# USB_Audio.net
KiCad netlist of a schematic drawn in Altium Designer
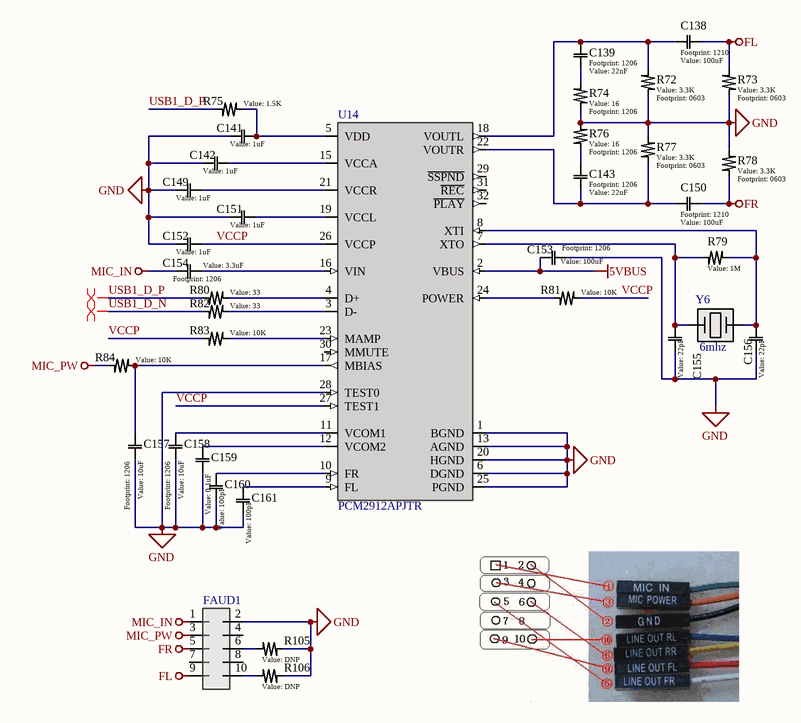
[diagram p0: USB_Audio.SchDoc]

(export (version "E")
  (design (tool "Eeschema 10.0.6"))
  (components
    (comp (ref "C138")
      (value "100uF")
      (footprint "1210")
      (fields
        (field (name "VOLTAGE") ">10V")
        (field (name "TOLERANCE") "10%")
        (field (name "Comment") "Generic Capacitor")
      )
      (libsource (lib "Capacitors") (part "Generic Capacitor"))
    )
    (comp (ref "C139")
      (value "22nF")
      (footprint "1206")
      (fields
        (field (name "VOLTAGE") ">10V")
        (field (name "TOLERANCE") "10%")
        (field (name "Comment") "Generic Capacitor")
      )
      (libsource (lib "Capacitors") (part "Generic Capacitor"))
    )
    (comp (ref "C141")
      (value "1uF")
      (footprint "0603")
      (fields
        (field (name "VOLTAGE") ">10V")
        (field (name "TOLERANCE") "10%")
        (field (name "Comment") "Generic Capacitor")
      )
      (libsource (lib "Capacitors") (part "Generic Capacitor"))
    )
    (comp (ref "C142")
      (value "1uF")
      (footprint "0603")
      (fields
        (field (name "VOLTAGE") ">10V")
        (field (name "TOLERANCE") "10%")
        (field (name "Comment") "Generic Capacitor")
      )
      (libsource (lib "Capacitors") (part "Generic Capacitor"))
    )
    (comp (ref "C143")
      (value "22nF")
      (footprint "1206")
      (fields
        (field (name "VOLTAGE") ">10V")
        (field (name "TOLERANCE") "10%")
        (field (name "Comment") "Generic Capacitor")
      )
      (libsource (lib "Capacitors") (part "Generic Capacitor"))
    )
    (comp (ref "C149")
      (value "1uF")
      (footprint "0603")
      (fields
        (field (name "VOLTAGE") ">10V")
        (field (name "TOLERANCE") "10%")
        (field (name "Comment") "Generic Capacitor")
      )
      (libsource (lib "Capacitors") (part "Generic Capacitor"))
    )
    (comp (ref "C150")
      (value "100uF")
      (footprint "1210")
      (fields
        (field (name "VOLTAGE") ">10V")
        (field (name "TOLERANCE") "10%")
        (field (name "Comment") "Generic Capacitor")
      )
      (libsource (lib "Capacitors") (part "Generic Capacitor"))
    )
    (comp (ref "C151")
      (value "1uF")
      (footprint "0603")
      (fields
        (field (name "VOLTAGE") ">10V")
        (field (name "TOLERANCE") "10%")
        (field (name "Comment") "Generic Capacitor")
      )
      (libsource (lib "Capacitors") (part "Generic Capacitor"))
    )
    (comp (ref "C152")
      (value "1uF")
      (footprint "0603")
      (fields
        (field (name "VOLTAGE") ">10V")
        (field (name "TOLERANCE") "10%")
        (field (name "Comment") "Generic Capacitor")
      )
      (libsource (lib "Capacitors") (part "Generic Capacitor"))
    )
    (comp (ref "C153")
      (value "100uF")
      (footprint "1206")
      (fields
        (field (name "VOLTAGE") ">10V")
        (field (name "TOLERANCE") "10%")
        (field (name "Comment") "Generic Capacitor")
      )
      (libsource (lib "Capacitors") (part "Generic Capacitor"))
    )
    (comp (ref "C154")
      (value "3.3uF")
      (footprint "1206")
      (fields
        (field (name "VOLTAGE") ">10V")
        (field (name "TOLERANCE") "10%")
        (field (name "Comment") "Generic Capacitor")
      )
      (libsource (lib "Capacitors") (part "Generic Capacitor"))
    )
    (comp (ref "C155")
      (value "22pF")
      (footprint "0603")
      (fields
        (field (name "VOLTAGE") ">10V")
        (field (name "TOLERANCE") "10%")
        (field (name "Comment") "Generic Capacitor")
      )
      (libsource (lib "Capacitors") (part "Generic Capacitor"))
    )
    (comp (ref "C156")
      (value "22pF")
      (footprint "0603")
      (fields
        (field (name "VOLTAGE") ">10V")
        (field (name "TOLERANCE") "10%")
        (field (name "Comment") "Generic Capacitor")
      )
      (libsource (lib "Capacitors") (part "Generic Capacitor"))
    )
    (comp (ref "C157")
      (value "10uF")
      (footprint "1206")
      (fields
        (field (name "VOLTAGE") ">10V")
        (field (name "TOLERANCE") "10%")
        (field (name "Comment") "Generic Capacitor")
      )
      (libsource (lib "Capacitors") (part "Generic Capacitor"))
    )
    (comp (ref "C158")
      (value "10uF")
      (footprint "1206")
      (fields
        (field (name "VOLTAGE") ">10V")
        (field (name "TOLERANCE") "10%")
        (field (name "Comment") "Generic Capacitor")
      )
      (libsource (lib "Capacitors") (part "Generic Capacitor"))
    )
    (comp (ref "C159")
      (value "0.1uF")
      (footprint "0603")
      (fields
        (field (name "VOLTAGE") ">10V")
        (field (name "TOLERANCE") "10%")
        (field (name "Comment") "Generic Capacitor")
      )
      (libsource (lib "Capacitors") (part "Generic Capacitor"))
    )
    (comp (ref "C160")
      (value "100pF")
      (footprint "0603")
      (fields
        (field (name "VOLTAGE") ">10V")
        (field (name "TOLERANCE") "10%")
        (field (name "Comment") "Generic Capacitor")
      )
      (libsource (lib "Capacitors") (part "Generic Capacitor"))
    )
    (comp (ref "C161")
      (value "100pF")
      (footprint "0603")
      (fields
        (field (name "VOLTAGE") ">10V")
        (field (name "TOLERANCE") "10%")
        (field (name "Comment") "Generic Capacitor")
      )
      (libsource (lib "Capacitors") (part "Generic Capacitor"))
    )
    (comp (ref "FAUD1")
      (value "10pinMobo")
      (footprint "10pinMobo")
      (description "10pin motherboard jack")
      (libsource (lib "Connectors") (part "10pinMobo"))
    )
    (comp (ref "R72")
      (value "3.3K")
      (footprint "0603")
      (fields
        (field (name "TOLERANCE") "1%")
        (field (name "POWER") "1/10W")
        (field (name "Comment") "Generic Resistor")
      )
      (libsource (lib "Resistors") (part "Generic Resistor"))
    )
    (comp (ref "R73")
      (value "3.3K")
      (footprint "0603")
      (fields
        (field (name "TOLERANCE") "1%")
        (field (name "POWER") "1/10W")
        (field (name "Comment") "Generic Resistor")
      )
      (libsource (lib "Resistors") (part "Generic Resistor"))
    )
    (comp (ref "R74")
      (value "16")
      (footprint "1206")
      (fields
        (field (name "TOLERANCE") "1%")
        (field (name "POWER") "1/10W")
        (field (name "Comment") "Generic Resistor")
      )
      (libsource (lib "Resistors") (part "Generic Resistor"))
    )
    (comp (ref "R75")
      (value "1.5K")
      (footprint "0603")
      (fields
        (field (name "TOLERANCE") "1%")
        (field (name "POWER") "1/10W")
        (field (name "Comment") "Generic Resistor")
      )
      (libsource (lib "Resistors") (part "Generic Resistor"))
    )
    (comp (ref "R76")
      (value "16")
      (footprint "1206")
      (fields
        (field (name "TOLERANCE") "1%")
        (field (name "POWER") "1/10W")
        (field (name "Comment") "Generic Resistor")
      )
      (libsource (lib "Resistors") (part "Generic Resistor"))
    )
    (comp (ref "R77")
      (value "3.3K")
      (footprint "0603")
      (fields
        (field (name "TOLERANCE") "1%")
        (field (name "POWER") "1/10W")
        (field (name "Comment") "Generic Resistor")
      )
      (libsource (lib "Resistors") (part "Generic Resistor"))
    )
    (comp (ref "R78")
      (value "3.3K")
      (footprint "0603")
      (fields
        (field (name "TOLERANCE") "1%")
        (field (name "POWER") "1/10W")
        (field (name "Comment") "Generic Resistor")
      )
      (libsource (lib "Resistors") (part "Generic Resistor"))
    )
    (comp (ref "R79")
      (value "1M")
      (footprint "0603")
      (fields
        (field (name "TOLERANCE") "1%")
        (field (name "POWER") "1/10W")
        (field (name "Comment") "Generic Resistor")
      )
      (libsource (lib "Resistors") (part "Generic Resistor"))
    )
    (comp (ref "R80")
      (value "33")
      (footprint "0603")
      (fields
        (field (name "TOLERANCE") "1%")
        (field (name "POWER") "1/10W")
        (field (name "Comment") "Generic Resistor")
      )
      (libsource (lib "Resistors") (part "Generic Resistor"))
    )
    (comp (ref "R81")
      (value "10K")
      (footprint "0603")
      (fields
        (field (name "TOLERANCE") "1%")
        (field (name "POWER") "1/10W")
        (field (name "Comment") "Generic Resistor")
      )
      (libsource (lib "Resistors") (part "Generic Resistor"))
    )
    (comp (ref "R82")
      (value "33")
      (footprint "0603")
      (fields
        (field (name "TOLERANCE") "1%")
        (field (name "POWER") "1/10W")
        (field (name "Comment") "Generic Resistor")
      )
      (libsource (lib "Resistors") (part "Generic Resistor"))
    )
    (comp (ref "R83")
      (value "10K")
      (footprint "0603")
      (fields
        (field (name "TOLERANCE") "1%")
        (field (name "POWER") "1/10W")
        (field (name "Comment") "Generic Resistor")
      )
      (libsource (lib "Resistors") (part "Generic Resistor"))
    )
    (comp (ref "R84")
      (value "10K")
      (footprint "0603")
      (fields
        (field (name "TOLERANCE") "1%")
        (field (name "POWER") "1/10W")
        (field (name "Comment") "Generic Resistor")
      )
      (libsource (lib "Resistors") (part "Generic Resistor"))
    )
    (comp (ref "R105")
      (value "DNP")
      (footprint "0603")
      (fields
        (field (name "TOLERANCE") "1%")
        (field (name "POWER") "1/10W")
        (field (name "Comment") "Generic Resistor")
      )
      (libsource (lib "Resistors") (part "Generic Resistor"))
    )
    (comp (ref "R106")
      (value "DNP")
      (footprint "0603")
      (fields
        (field (name "TOLERANCE") "1%")
        (field (name "POWER") "1/10W")
        (field (name "Comment") "Generic Resistor")
      )
      (libsource (lib "Resistors") (part "Generic Resistor"))
    )
    (comp (ref "U14")
      (value "PCM2912APJTR")
      (footprint "32-TQFP")
      (fields (field (name "MF") "Texas Instruments"))
      (libsource (lib "Misc ICs") (part "PCM2912APJTR"))
    )
    (comp (ref "Y6")
      (value "6mhz")
      (footprint "HC-49S-SMD")
      (description "6MHz Surface Mount Crystal 20pF ±20ppm ±30ppm HC-49S-SMD Crystals")
      (libsource (lib "Clock ICs") (part "H6OEL89CSC-SUGYLC-6M"))
    )
  )
  (nets
    (net (code "1") (name "/USB1_D_N") (class "Default")
      (node (ref "R82") (pin "2") (pinfunction "2_2") (pintype "passive"))
    )
    (net (code "2") (name "/USB1_D_P") (class "Default")
      (node (ref "R75") (pin "2") (pinfunction "2_2") (pintype "passive"))
      (node (ref "R80") (pin "2") (pinfunction "2_2") (pintype "passive"))
    )
    (net (code "3") (name "/VCCP") (class "Default")
      (node (ref "C152") (pin "2") (pinfunction "2_2") (pintype "passive"))
      (node (ref "R81") (pin "1") (pinfunction "1_1") (pintype "passive"))
      (node (ref "R83") (pin "2") (pinfunction "2_2") (pintype "passive"))
      (node (ref "U14") (pin "26") (pinfunction "VCCP_26") (pintype "power_in"))
      (node (ref "U14") (pin "27") (pinfunction "TEST1_27") (pintype "input"))
    )
    (net (code "4") (name "5VBUS") (class "Default")
      (node (ref "C153") (pin "1") (pinfunction "1_1") (pintype "passive"))
      (node (ref "U14") (pin "2") (pinfunction "VBUS_2") (pintype "input"))
    )
    (net (code "5") (name "FL") (class "Default")
      (node (ref "C138") (pin "1") (pinfunction "1_1") (pintype "passive"))
      (node (ref "FAUD1") (pin "9") (pinfunction "9_9") (pintype "passive"))
      (node (ref "R73") (pin "2") (pinfunction "2_2") (pintype "passive"))
    )
    (net (code "6") (name "FR") (class "Default")
      (node (ref "C150") (pin "1") (pinfunction "1_1") (pintype "passive"))
      (node (ref "FAUD1") (pin "5") (pinfunction "5_5") (pintype "passive"))
      (node (ref "R78") (pin "2") (pinfunction "2_2") (pintype "passive"))
    )
    (net (code "7") (name "GND") (class "Default")
      (node (ref "C141") (pin "1") (pinfunction "1_1") (pintype "passive"))
      (node (ref "C142") (pin "1") (pinfunction "1_1") (pintype "passive"))
      (node (ref "C149") (pin "1") (pinfunction "1_1") (pintype "passive"))
      (node (ref "C151") (pin "1") (pinfunction "1_1") (pintype "passive"))
      (node (ref "C152") (pin "1") (pinfunction "1_1") (pintype "passive"))
      (node (ref "C153") (pin "2") (pinfunction "2_2") (pintype "passive"))
      (node (ref "C155") (pin "2") (pinfunction "2_2") (pintype "passive"))
      (node (ref "C156") (pin "2") (pinfunction "2_2") (pintype "passive"))
      (node (ref "C157") (pin "2") (pinfunction "2_2") (pintype "passive"))
      (node (ref "C158") (pin "2") (pinfunction "2_2") (pintype "passive"))
      (node (ref "C159") (pin "2") (pinfunction "2_2") (pintype "passive"))
      (node (ref "C160") (pin "2") (pinfunction "2_2") (pintype "passive"))
      (node (ref "C161") (pin "2") (pinfunction "2_2") (pintype "passive"))
      (node (ref "FAUD1") (pin "2") (pinfunction "2_2") (pintype "passive"))
      (node (ref "R105") (pin "1") (pinfunction "1_1") (pintype "passive"))
      (node (ref "R106") (pin "1") (pinfunction "1_1") (pintype "passive"))
      (node (ref "R72") (pin "1") (pinfunction "1_1") (pintype "passive"))
      (node (ref "R73") (pin "1") (pinfunction "1_1") (pintype "passive"))
      (node (ref "R74") (pin "1") (pinfunction "1_1") (pintype "passive"))
      (node (ref "R76") (pin "1") (pinfunction "1_1") (pintype "passive"))
      (node (ref "R77") (pin "1") (pinfunction "1_1") (pintype "passive"))
      (node (ref "R78") (pin "1") (pinfunction "1_1") (pintype "passive"))
      (node (ref "U14") (pin "1") (pinfunction "BGND_1") (pintype "power_in"))
      (node (ref "U14") (pin "13") (pinfunction "AGND_13") (pintype "power_in"))
      (node (ref "U14") (pin "20") (pinfunction "HGND_20") (pintype "power_in"))
      (node (ref "U14") (pin "25") (pinfunction "PGND_25") (pintype "power_in"))
      (node (ref "U14") (pin "28") (pinfunction "TEST0_28") (pintype "input"))
      (node (ref "U14") (pin "6") (pinfunction "DGND_6") (pintype "power_in"))
    )
    (net (code "8") (name "MIC_IN") (class "Default")
      (node (ref "C154") (pin "2") (pinfunction "2_2") (pintype "passive"))
      (node (ref "FAUD1") (pin "1") (pinfunction "1_1") (pintype "passive"))
    )
    (net (code "9") (name "MIC_PW") (class "Default")
      (node (ref "FAUD1") (pin "3") (pinfunction "3_3") (pintype "passive"))
      (node (ref "R84") (pin "2") (pinfunction "2_2") (pintype "passive"))
    )
    (net (code "10") (name "Net-(C139-Pad2)") (class "Default")
      (node (ref "C139") (pin "2") (pinfunction "2_2") (pintype "passive"))
      (node (ref "R74") (pin "2") (pinfunction "2_2") (pintype "passive"))
    )
    (net (code "11") (name "Net-(C143-Pad2)") (class "Default")
      (node (ref "C143") (pin "2") (pinfunction "2_2") (pintype "passive"))
      (node (ref "R76") (pin "2") (pinfunction "2_2") (pintype "passive"))
    )
    (net (code "12") (name "Net-(FAUD1-Pad6)") (class "Default")
      (node (ref "FAUD1") (pin "6") (pinfunction "6_6") (pintype "passive"))
      (node (ref "R105") (pin "2") (pinfunction "2_2") (pintype "passive"))
    )
    (net (code "13") (name "Net-(FAUD1-Pad10)") (class "Default")
      (node (ref "FAUD1") (pin "10") (pinfunction "10_10") (pintype "passive"))
      (node (ref "R106") (pin "2") (pinfunction "2_2") (pintype "passive"))
    )
    (net (code "14") (name "Net-(U14-D+)") (class "Default")
      (node (ref "R80") (pin "1") (pinfunction "1_1") (pintype "passive"))
      (node (ref "U14") (pin "4") (pinfunction "D+_4") (pintype "bidirectional"))
    )
    (net (code "15") (name "Net-(U14-D-)") (class "Default")
      (node (ref "R82") (pin "1") (pinfunction "1_1") (pintype "passive"))
      (node (ref "U14") (pin "3") (pinfunction "D-_3") (pintype "bidirectional"))
    )
    (net (code "16") (name "Net-(U14-FL)") (class "Default")
      (node (ref "C161") (pin "1") (pinfunction "1_1") (pintype "passive"))
      (node (ref "U14") (pin "9") (pinfunction "FL_9") (pintype "input"))
    )
    (net (code "17") (name "Net-(U14-FR)") (class "Default")
      (node (ref "C160") (pin "1") (pinfunction "1_1") (pintype "passive"))
      (node (ref "U14") (pin "10") (pinfunction "FR_10") (pintype "input"))
    )
    (net (code "18") (name "Net-(U14-MAMP)") (class "Default")
      (node (ref "R83") (pin "1") (pinfunction "1_1") (pintype "passive"))
      (node (ref "U14") (pin "23") (pinfunction "MAMP_23") (pintype "input"))
    )
    (net (code "19") (name "Net-(U14-MBIAS)") (class "Default")
      (node (ref "C157") (pin "1") (pinfunction "1_1") (pintype "passive"))
      (node (ref "R84") (pin "1") (pinfunction "1_1") (pintype "passive"))
      (node (ref "U14") (pin "17") (pinfunction "MBIAS_17") (pintype "output"))
    )
    (net (code "20") (name "Net-(U14-POWER)") (class "Default")
      (node (ref "R81") (pin "2") (pinfunction "2_2") (pintype "passive"))
      (node (ref "U14") (pin "24") (pinfunction "POWER_24") (pintype "input"))
    )
    (net (code "21") (name "Net-(U14-VCCA)") (class "Default")
      (node (ref "C142") (pin "2") (pinfunction "2_2") (pintype "passive"))
      (node (ref "U14") (pin "15") (pinfunction "VCCA_15") (pintype "power_in"))
    )
    (net (code "22") (name "Net-(U14-VCCL)") (class "Default")
      (node (ref "C151") (pin "2") (pinfunction "2_2") (pintype "passive"))
      (node (ref "U14") (pin "19") (pinfunction "VCCL_19") (pintype "power_in"))
    )
    (net (code "23") (name "Net-(U14-VCCR)") (class "Default")
      (node (ref "C149") (pin "2") (pinfunction "2_2") (pintype "passive"))
      (node (ref "U14") (pin "21") (pinfunction "VCCR_21") (pintype "power_in"))
    )
    (net (code "24") (name "Net-(U14-VCOM1)") (class "Default")
      (node (ref "C158") (pin "1") (pinfunction "1_1") (pintype "passive"))
      (node (ref "U14") (pin "11") (pinfunction "VCOM1_11") (pintype "power_in"))
    )
    (net (code "25") (name "Net-(U14-VCOM2)") (class "Default")
      (node (ref "C159") (pin "1") (pinfunction "1_1") (pintype "passive"))
      (node (ref "U14") (pin "12") (pinfunction "VCOM2_12") (pintype "power_in"))
    )
    (net (code "26") (name "Net-(U14-VDD)") (class "Default")
      (node (ref "C141") (pin "2") (pinfunction "2_2") (pintype "passive"))
      (node (ref "R75") (pin "1") (pinfunction "1_1") (pintype "passive"))
      (node (ref "U14") (pin "5") (pinfunction "VDD_5") (pintype "power_in"))
    )
    (net (code "27") (name "Net-(U14-VIN)") (class "Default")
      (node (ref "C154") (pin "1") (pinfunction "1_1") (pintype "passive"))
      (node (ref "U14") (pin "16") (pinfunction "VIN_16") (pintype "input"))
    )
    (net (code "28") (name "Net-(U14-VOUTL)") (class "Default")
      (node (ref "C138") (pin "2") (pinfunction "2_2") (pintype "passive"))
      (node (ref "C139") (pin "1") (pinfunction "1_1") (pintype "passive"))
      (node (ref "R72") (pin "2") (pinfunction "2_2") (pintype "passive"))
      (node (ref "U14") (pin "18") (pinfunction "VOUTL_18") (pintype "output"))
    )
    (net (code "29") (name "Net-(U14-VOUTR)") (class "Default")
      (node (ref "C143") (pin "1") (pinfunction "1_1") (pintype "passive"))
      (node (ref "C150") (pin "2") (pinfunction "2_2") (pintype "passive"))
      (node (ref "R77") (pin "2") (pinfunction "2_2") (pintype "passive"))
      (node (ref "U14") (pin "22") (pinfunction "VOUTR_22") (pintype "output"))
    )
    (net (code "30") (name "Net-(U14-XTI)") (class "Default")
      (node (ref "C156") (pin "1") (pinfunction "1_1") (pintype "passive"))
      (node (ref "R79") (pin "2") (pinfunction "2_2") (pintype "passive"))
      (node (ref "U14") (pin "8") (pinfunction "XTI_8") (pintype "input"))
      (node (ref "Y6") (pin "2") (pintype "passive"))
    )
    (net (code "31") (name "Net-(U14-XTO)") (class "Default")
      (node (ref "C155") (pin "1") (pinfunction "1_1") (pintype "passive"))
      (node (ref "R79") (pin "1") (pinfunction "1_1") (pintype "passive"))
      (node (ref "U14") (pin "7") (pinfunction "XTO_7") (pintype "output"))
      (node (ref "Y6") (pin "1") (pintype "passive"))
    )
    (net (code "32") (name "unconnected-(FAUD1-Pad4)") (class "Default")
      (node (ref "FAUD1") (pin "4") (pinfunction "4_4") (pintype "passive"))
    )
    (net (code "33") (name "unconnected-(FAUD1-Pad7)") (class "Default")
      (node (ref "FAUD1") (pin "7") (pinfunction "7_7") (pintype "passive"))
    )
    (net (code "34") (name "unconnected-(FAUD1-Pad8)") (class "Default")
      (node (ref "FAUD1") (pin "8") (pinfunction "8_8") (pintype "passive"))
    )
    (net (code "35") (name "unconnected-(U14-MMUTE-Pad30)") (class "Default")
      (node (ref "U14") (pin "30") (pinfunction "MMUTE_30") (pintype "input"))
    )
    (net (code "36") (name "unconnected-(U14-~{PLAY}-Pad32)") (class "Default")
      (node (ref "U14") (pin "32") (pinfunction "~{PLAY}_32") (pintype "output"))
    )
    (net (code "37") (name "unconnected-(U14-~{REC}-Pad31)") (class "Default")
      (node (ref "U14") (pin "31") (pinfunction "~{REC}_31") (pintype "output"))
    )
    (net (code "38") (name "unconnected-(U14-~{SSPND}-Pad29)") (class "Default")
      (node (ref "U14") (pin "29") (pinfunction "~{SSPND}_29") (pintype "output"))
    )
  )
)
